# 7ch_op_amp_board_v31.net
KiCad netlist of a schematic drawn in EAGLE
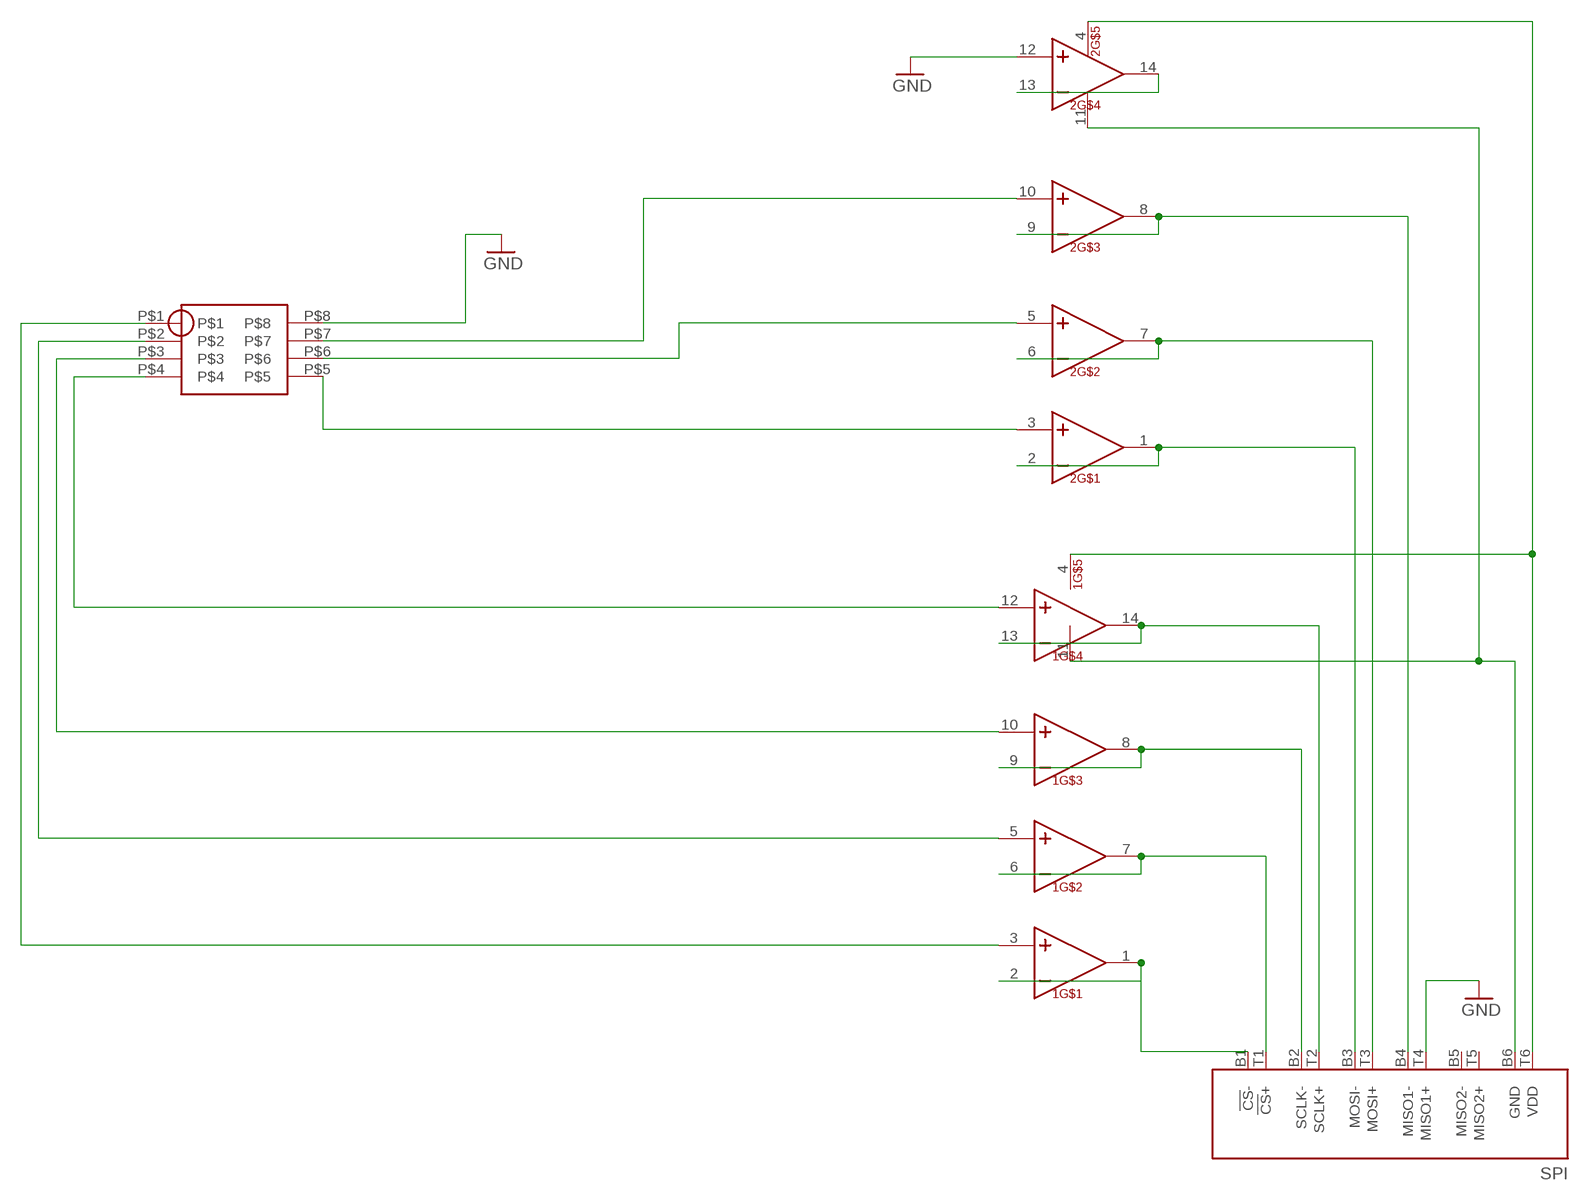
[diagram p0: schematic, sheet 1]

(export (version "E")
  (design (tool "Eeschema 10.0.6"))
  (components
    (comp (ref "1")
      (value "TL074-TSSOP")
      (footprint "eagle-import:TSSOP14")
      (libsource (lib "eagle-import") (part "TL074-TSSOP"))
    )
    (comp (ref "2")
      (value "TL074-TSSOP")
      (footprint "eagle-import:TSSOP14")
      (libsource (lib "eagle-import") (part "TL074-TSSOP"))
    )
    (comp (ref "B")
      (value "853-PPP-8-SOLDERTAIL")
      (footprint "eagle-import:853-PPP-8")
      (libsource (lib "eagle-import") (part "853-PPP-8-SOLDERTAIL"))
    )
    (comp (ref "SPI")
      (value "RHD2000-CABLE-AMP-SIDE")
      (footprint "eagle-import:OMNETICS_PZN-12-AA")
      (libsource (lib "eagle-import") (part "RHD2000-CABLE-AMP-SIDE"))
    )
  )
  (nets
    (net (code "1") (name "GND") (class "Default")
      (node (ref "2") (pin "12") (pinfunction "IN+_12") (pintype "input"))
      (node (ref "B") (pin "P$8") (pinfunction "P$8_P$8") (pintype "bidirectional"))
      (node (ref "SPI") (pin "T4") (pinfunction "MISO1+_T4") (pintype "bidirectional"))
    )
    (net (code "2") (name "Net-(1A-IN+)") (class "Default")
      (node (ref "1") (pin "3") (pinfunction "IN+_3") (pintype "input"))
      (node (ref "B") (pin "P$1") (pinfunction "P$1_P$1") (pintype "bidirectional"))
    )
    (net (code "3") (name "Net-(1A-IN-)") (class "Default")
      (node (ref "1") (pin "1") (pinfunction "OUT_1") (pintype "output"))
      (node (ref "1") (pin "2") (pinfunction "IN-_2") (pintype "input"))
      (node (ref "SPI") (pin "B1") (pinfunction "~{CS}-_B1") (pintype "bidirectional"))
    )
    (net (code "4") (name "Net-(1B-IN+)") (class "Default")
      (node (ref "1") (pin "5") (pinfunction "IN+_5") (pintype "input"))
      (node (ref "B") (pin "P$2") (pinfunction "P$2_P$2") (pintype "bidirectional"))
    )
    (net (code "5") (name "Net-(1B-IN-)") (class "Default")
      (node (ref "1") (pin "6") (pinfunction "IN-_6") (pintype "input"))
      (node (ref "1") (pin "7") (pinfunction "OUT_7") (pintype "output"))
      (node (ref "SPI") (pin "T1") (pinfunction "~{CS}+_T1") (pintype "bidirectional"))
    )
    (net (code "6") (name "Net-(1C-IN+)") (class "Default")
      (node (ref "1") (pin "10") (pinfunction "IN+_10") (pintype "input"))
      (node (ref "B") (pin "P$3") (pinfunction "P$3_P$3") (pintype "bidirectional"))
    )
    (net (code "7") (name "Net-(1C-IN-)") (class "Default")
      (node (ref "1") (pin "8") (pinfunction "OUT_8") (pintype "output"))
      (node (ref "1") (pin "9") (pinfunction "IN-_9") (pintype "input"))
      (node (ref "SPI") (pin "B2") (pinfunction "SCLK-_B2") (pintype "bidirectional"))
    )
    (net (code "8") (name "Net-(1D-IN+)") (class "Default")
      (node (ref "1") (pin "12") (pinfunction "IN+_12") (pintype "input"))
      (node (ref "B") (pin "P$4") (pinfunction "P$4_P$4") (pintype "bidirectional"))
    )
    (net (code "9") (name "Net-(1D-IN-)") (class "Default")
      (node (ref "1") (pin "13") (pinfunction "IN-_13") (pintype "input"))
      (node (ref "1") (pin "14") (pinfunction "OUT_14") (pintype "output"))
      (node (ref "SPI") (pin "T2") (pinfunction "SCLK+_T2") (pintype "bidirectional"))
    )
    (net (code "10") (name "Net-(1E-VCC+)") (class "Default")
      (node (ref "1") (pin "4") (pinfunction "VCC+_4") (pintype "power_in"))
      (node (ref "2") (pin "4") (pinfunction "VCC+_4") (pintype "power_in"))
      (node (ref "SPI") (pin "T6") (pinfunction "VDD_T6") (pintype "bidirectional"))
    )
    (net (code "11") (name "Net-(1E-VCC-)") (class "Default")
      (node (ref "1") (pin "11") (pinfunction "VCC-_11") (pintype "power_in"))
      (node (ref "2") (pin "11") (pinfunction "VCC-_11") (pintype "power_in"))
      (node (ref "SPI") (pin "B6") (pinfunction "GND_B6") (pintype "power_in"))
    )
    (net (code "12") (name "Net-(2A-IN+)") (class "Default")
      (node (ref "2") (pin "3") (pinfunction "IN+_3") (pintype "input"))
      (node (ref "B") (pin "P$5") (pinfunction "P$5_P$5") (pintype "bidirectional"))
    )
    (net (code "13") (name "Net-(2A-IN-)") (class "Default")
      (node (ref "2") (pin "1") (pinfunction "OUT_1") (pintype "output"))
      (node (ref "2") (pin "2") (pinfunction "IN-_2") (pintype "input"))
      (node (ref "SPI") (pin "B3") (pinfunction "MOSI-_B3") (pintype "bidirectional"))
    )
    (net (code "14") (name "Net-(2B-IN+)") (class "Default")
      (node (ref "2") (pin "5") (pinfunction "IN+_5") (pintype "input"))
      (node (ref "B") (pin "P$6") (pinfunction "P$6_P$6") (pintype "bidirectional"))
    )
    (net (code "15") (name "Net-(2B-IN-)") (class "Default")
      (node (ref "2") (pin "6") (pinfunction "IN-_6") (pintype "input"))
      (node (ref "2") (pin "7") (pinfunction "OUT_7") (pintype "output"))
      (node (ref "SPI") (pin "T3") (pinfunction "MOSI+_T3") (pintype "bidirectional"))
    )
    (net (code "16") (name "Net-(2C-IN+)") (class "Default")
      (node (ref "2") (pin "10") (pinfunction "IN+_10") (pintype "input"))
      (node (ref "B") (pin "P$7") (pinfunction "P$7_P$7") (pintype "bidirectional"))
    )
    (net (code "17") (name "Net-(2C-IN-)") (class "Default")
      (node (ref "2") (pin "8") (pinfunction "OUT_8") (pintype "output"))
      (node (ref "2") (pin "9") (pinfunction "IN-_9") (pintype "input"))
      (node (ref "SPI") (pin "B4") (pinfunction "MISO1-_B4") (pintype "bidirectional"))
    )
    (net (code "18") (name "Net-(2D-IN-)") (class "Default")
      (node (ref "2") (pin "13") (pinfunction "IN-_13") (pintype "input"))
      (node (ref "2") (pin "14") (pinfunction "OUT_14") (pintype "output"))
    )
    (net (code "19") (name "unconnected-(SPI-MISO2+-PadT5)") (class "Default")
      (node (ref "SPI") (pin "T5") (pinfunction "MISO2+_T5") (pintype "bidirectional"))
    )
    (net (code "20") (name "unconnected-(SPI-MISO2--PadB5)") (class "Default")
      (node (ref "SPI") (pin "B5") (pinfunction "MISO2-_B5") (pintype "bidirectional"))
    )
  )
)
